# fl5_fl9_modv1.net
KiCad netlist of a schematic drawn in EAGLE
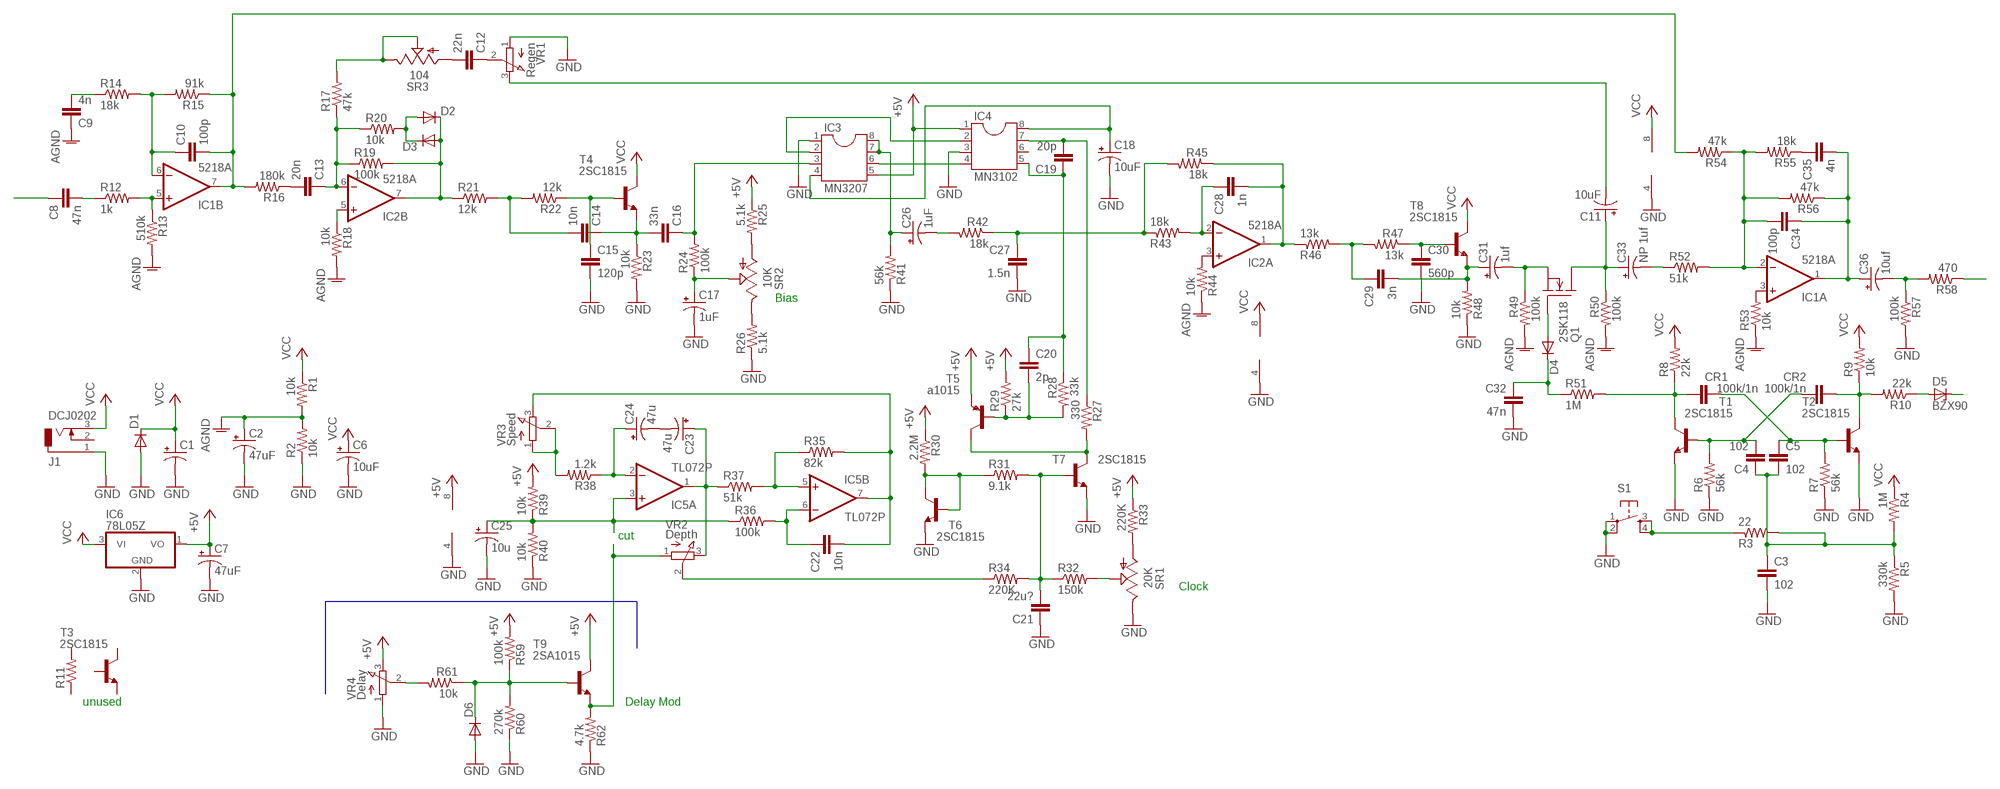
[diagram p0: schematic, sheet 1]

(export (version "E")
  (design (tool "Eeschema 10.0.6"))
  (components
    (comp (ref "C1")
      (value "CPOL-USE3.5-8")
      (footprint "eagle-import:E3,5-8")
      (libsource (lib "eagle-import") (part "CPOL-USE3.5-8"))
    )
    (comp (ref "C2")
      (value "47uF")
      (footprint "eagle-import:E1,8-4")
      (libsource (lib "eagle-import") (part "CPOL-USE1.8-4"))
    )
    (comp (ref "C3")
      (value "102")
      (footprint "eagle-import:C025-024X044")
      (libsource (lib "eagle-import") (part "C-EU025-024X044"))
    )
    (comp (ref "C4")
      (value "102")
      (footprint "eagle-import:C025-024X044")
      (libsource (lib "eagle-import") (part "C-EU025-024X044"))
    )
    (comp (ref "C5")
      (value "102")
      (footprint "eagle-import:C025-024X044")
      (libsource (lib "eagle-import") (part "C-EU025-024X044"))
    )
    (comp (ref "C6")
      (value "10uF")
      (footprint "eagle-import:E1,8-4")
      (libsource (lib "eagle-import") (part "CPOL-USE1.8-4"))
    )
    (comp (ref "C7")
      (value "47uF")
      (footprint "eagle-import:E1,8-4")
      (libsource (lib "eagle-import") (part "CPOL-USE1.8-4"))
    )
    (comp (ref "C8")
      (value "47n")
      (footprint "eagle-import:C050-025X075")
      (libsource (lib "eagle-import") (part "C-EU050-025X075"))
    )
    (comp (ref "C9")
      (value "4n")
      (footprint "eagle-import:C050-025X075")
      (libsource (lib "eagle-import") (part "C-EU050-025X075"))
    )
    (comp (ref "C10")
      (value "100p")
      (footprint "eagle-import:C025-024X044")
      (libsource (lib "eagle-import") (part "C-EU025-024X044"))
    )
    (comp (ref "C11")
      (value "10uF")
      (footprint "eagle-import:E1,8-4")
      (libsource (lib "eagle-import") (part "CPOL-USE1.8-4"))
    )
    (comp (ref "C12")
      (value "22n")
      (footprint "eagle-import:C050-025X075")
      (libsource (lib "eagle-import") (part "C-EU050-025X075"))
    )
    (comp (ref "C13")
      (value "20n")
      (footprint "eagle-import:C050-025X075")
      (libsource (lib "eagle-import") (part "C-EU050-025X075"))
    )
    (comp (ref "C14")
      (value "10n")
      (footprint "eagle-import:C050-025X075")
      (libsource (lib "eagle-import") (part "C-EU050-025X075"))
    )
    (comp (ref "C15")
      (value "120p")
      (footprint "eagle-import:C050-024X044")
      (libsource (lib "eagle-import") (part "C-EU050-024X044"))
    )
    (comp (ref "C16")
      (value "33n")
      (footprint "eagle-import:C050-025X075")
      (libsource (lib "eagle-import") (part "C-EU050-025X075"))
    )
    (comp (ref "C17")
      (value "1uF")
      (footprint "eagle-import:E1,8-4")
      (libsource (lib "eagle-import") (part "CPOL-USE1.8-4"))
    )
    (comp (ref "C18")
      (value "10uF")
      (footprint "eagle-import:E1,8-4")
      (libsource (lib "eagle-import") (part "CPOL-USE1.8-4"))
    )
    (comp (ref "C19")
      (value "20p")
      (footprint "eagle-import:C025-024X044")
      (libsource (lib "eagle-import") (part "C-EU025-024X044"))
    )
    (comp (ref "C20")
      (value "2p")
      (footprint "eagle-import:C025-024X044")
      (libsource (lib "eagle-import") (part "C-EU025-024X044"))
    )
    (comp (ref "C21")
      (value "22u?")
      (footprint "eagle-import:C025-024X044")
      (libsource (lib "eagle-import") (part "C-EU025-024X044"))
    )
    (comp (ref "C22")
      (value "10n")
      (footprint "eagle-import:C050-025X075")
      (libsource (lib "eagle-import") (part "C-EU050-025X075"))
    )
    (comp (ref "C23")
      (value "47u")
      (footprint "eagle-import:E2,5-7")
      (libsource (lib "eagle-import") (part "CPOL-USE2.5-7"))
    )
    (comp (ref "C24")
      (value "47u")
      (footprint "eagle-import:E2,5-7")
      (libsource (lib "eagle-import") (part "CPOL-USE2.5-7"))
    )
    (comp (ref "C25")
      (value "10u")
      (footprint "eagle-import:E1,8-4")
      (libsource (lib "eagle-import") (part "CPOL-USE1.8-4"))
    )
    (comp (ref "C26")
      (value "1uF")
      (footprint "eagle-import:E1,8-4")
      (libsource (lib "eagle-import") (part "CPOL-USE1.8-4"))
    )
    (comp (ref "C27")
      (value "1.5n")
      (footprint "eagle-import:C050-025X075")
      (libsource (lib "eagle-import") (part "C-EU050-025X075"))
    )
    (comp (ref "C28")
      (value "1n")
      (footprint "eagle-import:C050-025X075")
      (libsource (lib "eagle-import") (part "C-EU050-025X075"))
    )
    (comp (ref "C29")
      (value "3n")
      (footprint "eagle-import:C050-025X075")
      (libsource (lib "eagle-import") (part "C-EU050-025X075"))
    )
    (comp (ref "C30")
      (value "560p")
      (footprint "eagle-import:C050-024X044")
      (libsource (lib "eagle-import") (part "C-EU050-024X044"))
    )
    (comp (ref "C31")
      (value "1uf")
      (footprint "eagle-import:E1,8-4")
      (libsource (lib "eagle-import") (part "CPOL-USE1.8-4"))
    )
    (comp (ref "C32")
      (value "47n")
      (footprint "eagle-import:C050-025X075")
      (libsource (lib "eagle-import") (part "C-EU050-025X075"))
    )
    (comp (ref "C33")
      (value "NP 1uf")
      (footprint "eagle-import:E1,8-4")
      (libsource (lib "eagle-import") (part "CPOL-USE1.8-4"))
    )
    (comp (ref "C34")
      (value "100p")
      (footprint "eagle-import:C025-024X044")
      (libsource (lib "eagle-import") (part "C-EU025-024X044"))
    )
    (comp (ref "C35")
      (value "4n")
      (footprint "eagle-import:C050-025X075")
      (libsource (lib "eagle-import") (part "C-EU050-025X075"))
    )
    (comp (ref "C36")
      (value "10uf")
      (footprint "eagle-import:E1,8-4")
      (libsource (lib "eagle-import") (part "CPOL-USE1.8-4"))
    )
    (comp (ref "CR1")
      (value "100k/1n")
      (footprint "eagle-import:C025-024X044")
      (libsource (lib "eagle-import") (part "C-EU025-024X044"))
    )
    (comp (ref "CR2")
      (value "100k/1n")
      (footprint "eagle-import:C025-024X044")
      (libsource (lib "eagle-import") (part "C-EU025-024X044"))
    )
    (comp (ref "D1")
      (value "DIODE-C1702-05")
      (footprint "eagle-import:C1702-05")
      (libsource (lib "eagle-import") (part "DIODE-C1702-05"))
    )
    (comp (ref "D2")
      (value "DIODE-D-5")
      (footprint "eagle-import:D-5")
      (libsource (lib "eagle-import") (part "DIODE-D-5"))
    )
    (comp (ref "D3")
      (value "DIODE-D-5")
      (footprint "eagle-import:D-5")
      (libsource (lib "eagle-import") (part "DIODE-D-5"))
    )
    (comp (ref "D4")
      (value "DIODE-D-5")
      (footprint "eagle-import:D-5")
      (libsource (lib "eagle-import") (part "DIODE-D-5"))
    )
    (comp (ref "D5")
      (value "BZX90")
      (footprint "eagle-import:DO34Z7")
      (libsource (lib "eagle-import") (part "BZX90"))
    )
    (comp (ref "D6")
      (value "DIODE-D-5")
      (footprint "eagle-import:D-5")
      (libsource (lib "eagle-import") (part "DIODE-D-5"))
    )
    (comp (ref "IC1")
      (value "5218A")
      (footprint "eagle-import:DIL08")
      (libsource (lib "eagle-import") (part "4558NLM"))
    )
    (comp (ref "IC2")
      (value "5218A")
      (footprint "eagle-import:DIL08")
      (libsource (lib "eagle-import") (part "4558NLM"))
    )
    (comp (ref "IC3")
      (value "MN3207")
      (footprint "eagle-import:DIL08")
      (libsource (lib "eagle-import") (part "DIL8"))
    )
    (comp (ref "IC4")
      (value "MN3102")
      (footprint "eagle-import:DIL08")
      (libsource (lib "eagle-import") (part "DIL8"))
    )
    (comp (ref "IC5")
      (value "TL072P")
      (footprint "eagle-import:DIL08")
      (libsource (lib "eagle-import") (part "TL072P"))
    )
    (comp (ref "IC6")
      (value "78L05Z")
      (footprint "eagle-import:TO92")
      (libsource (lib "eagle-import") (part "78ZL05"))
    )
    (comp (ref "J1")
      (value "DCJ0202")
      (footprint "eagle-import:DCJ0202")
      (libsource (lib "eagle-import") (part "DCJ0202"))
    )
    (comp (ref "Q1")
      (value "2SK118")
      (footprint "eagle-import:TO237")
      (libsource (lib "eagle-import") (part "VN2222KM"))
    )
    (comp (ref "R1")
      (value "10k")
      (footprint "eagle-import:0204_5")
      (libsource (lib "eagle-import") (part "R-US_0204/5"))
    )
    (comp (ref "R2")
      (value "10k")
      (footprint "eagle-import:0204_5")
      (libsource (lib "eagle-import") (part "R-US_0204/5"))
    )
    (comp (ref "R3")
      (value "22")
      (footprint "eagle-import:0204_5")
      (libsource (lib "eagle-import") (part "R-US_0204/5"))
    )
    (comp (ref "R4")
      (value "1M")
      (footprint "eagle-import:0204_5")
      (libsource (lib "eagle-import") (part "R-US_0204/5"))
    )
    (comp (ref "R5")
      (value "330k")
      (footprint "eagle-import:0204_5")
      (libsource (lib "eagle-import") (part "R-US_0204/5"))
    )
    (comp (ref "R6")
      (value "56k")
      (footprint "eagle-import:0204_5")
      (libsource (lib "eagle-import") (part "R-US_0204/5"))
    )
    (comp (ref "R7")
      (value "56k")
      (footprint "eagle-import:0204_5")
      (libsource (lib "eagle-import") (part "R-US_0204/5"))
    )
    (comp (ref "R8")
      (value "22k")
      (footprint "eagle-import:0204_5")
      (libsource (lib "eagle-import") (part "R-US_0204/5"))
    )
    (comp (ref "R9")
      (value "10k")
      (footprint "eagle-import:0204_5")
      (libsource (lib "eagle-import") (part "R-US_0204/5"))
    )
    (comp (ref "R10")
      (value "22k")
      (footprint "eagle-import:0204_5")
      (libsource (lib "eagle-import") (part "R-US_0204/5"))
    )
    (comp (ref "R11")
      (value "R-US_0204/5")
      (footprint "eagle-import:0204_5")
      (libsource (lib "eagle-import") (part "R-US_0204/5"))
    )
    (comp (ref "R12")
      (value "1k")
      (footprint "eagle-import:0204_5")
      (libsource (lib "eagle-import") (part "R-US_0204/5"))
    )
    (comp (ref "R13")
      (value "510k")
      (footprint "eagle-import:0204_5")
      (libsource (lib "eagle-import") (part "R-US_0204/5"))
    )
    (comp (ref "R14")
      (value "18k")
      (footprint "eagle-import:0204_5")
      (libsource (lib "eagle-import") (part "R-US_0204/5"))
    )
    (comp (ref "R15")
      (value "91k")
      (footprint "eagle-import:0204_5")
      (libsource (lib "eagle-import") (part "R-US_0204/5"))
    )
    (comp (ref "R16")
      (value "180k")
      (footprint "eagle-import:0204_5")
      (libsource (lib "eagle-import") (part "R-US_0204/5"))
    )
    (comp (ref "R17")
      (value "47k")
      (footprint "eagle-import:0204_5")
      (libsource (lib "eagle-import") (part "R-US_0204/5"))
    )
    (comp (ref "R18")
      (value "10k")
      (footprint "eagle-import:0204_5")
      (libsource (lib "eagle-import") (part "R-US_0204/5"))
    )
    (comp (ref "R19")
      (value "100k")
      (footprint "eagle-import:0204_5")
      (libsource (lib "eagle-import") (part "R-US_0204/5"))
    )
    (comp (ref "R20")
      (value "10k")
      (footprint "eagle-import:0204_5")
      (libsource (lib "eagle-import") (part "R-US_0204/5"))
    )
    (comp (ref "R21")
      (value "12k")
      (footprint "eagle-import:0204_5")
      (libsource (lib "eagle-import") (part "R-US_0204/5"))
    )
    (comp (ref "R22")
      (value "12k")
      (footprint "eagle-import:0204_5")
      (libsource (lib "eagle-import") (part "R-US_0204/5"))
    )
    (comp (ref "R23")
      (value "10k")
      (footprint "eagle-import:0204_5")
      (libsource (lib "eagle-import") (part "R-US_0204/5"))
    )
    (comp (ref "R24")
      (value "100k")
      (footprint "eagle-import:0204_5")
      (libsource (lib "eagle-import") (part "R-US_0204/5"))
    )
    (comp (ref "R25")
      (value "5.1k")
      (footprint "eagle-import:0204_5")
      (libsource (lib "eagle-import") (part "R-US_0204/5"))
    )
    (comp (ref "R26")
      (value "5.1k")
      (footprint "eagle-import:0204_5")
      (libsource (lib "eagle-import") (part "R-US_0204/5"))
    )
    (comp (ref "R27")
      (value "330")
      (footprint "eagle-import:0204_5")
      (libsource (lib "eagle-import") (part "R-US_0204/5"))
    )
    (comp (ref "R28")
      (value "33k")
      (footprint "eagle-import:0204_5")
      (libsource (lib "eagle-import") (part "R-US_0204/5"))
    )
    (comp (ref "R29")
      (value "27k")
      (footprint "eagle-import:0204_5")
      (libsource (lib "eagle-import") (part "R-US_0204/5"))
    )
    (comp (ref "R30")
      (value "2.2M")
      (footprint "eagle-import:0204_5")
      (libsource (lib "eagle-import") (part "R-US_0204/5"))
    )
    (comp (ref "R31")
      (value "9.1k")
      (footprint "eagle-import:0204_5")
      (libsource (lib "eagle-import") (part "R-US_0204/5"))
    )
    (comp (ref "R32")
      (value "150k")
      (footprint "eagle-import:0204_5")
      (libsource (lib "eagle-import") (part "R-US_0204/5"))
    )
    (comp (ref "R33")
      (value "220K")
      (footprint "eagle-import:0204_5")
      (libsource (lib "eagle-import") (part "R-US_0204/5"))
    )
    (comp (ref "R34")
      (value "220K")
      (footprint "eagle-import:0204_5")
      (libsource (lib "eagle-import") (part "R-US_0204/5"))
    )
    (comp (ref "R35")
      (value "82k")
      (footprint "eagle-import:0204_5")
      (libsource (lib "eagle-import") (part "R-US_0204/5"))
    )
    (comp (ref "R36")
      (value "100k")
      (footprint "eagle-import:0204_5")
      (libsource (lib "eagle-import") (part "R-US_0204/5"))
    )
    (comp (ref "R37")
      (value "51k")
      (footprint "eagle-import:0204_5")
      (libsource (lib "eagle-import") (part "R-US_0204/5"))
    )
    (comp (ref "R38")
      (value "1.2k")
      (footprint "eagle-import:0204_5")
      (libsource (lib "eagle-import") (part "R-US_0204/5"))
    )
    (comp (ref "R39")
      (value "10k")
      (footprint "eagle-import:0204_5")
      (libsource (lib "eagle-import") (part "R-US_0204/5"))
    )
    (comp (ref "R40")
      (value "10k")
      (footprint "eagle-import:0204_5")
      (libsource (lib "eagle-import") (part "R-US_0204/5"))
    )
    (comp (ref "R41")
      (value "56k")
      (footprint "eagle-import:0204_5")
      (libsource (lib "eagle-import") (part "R-US_0204/5"))
    )
    (comp (ref "R42")
      (value "18k")
      (footprint "eagle-import:0204_5")
      (libsource (lib "eagle-import") (part "R-US_0204/5"))
    )
    (comp (ref "R43")
      (value "18k")
      (footprint "eagle-import:0204_5")
      (libsource (lib "eagle-import") (part "R-US_0204/5"))
    )
    (comp (ref "R44")
      (value "10k")
      (footprint "eagle-import:0204_5")
      (libsource (lib "eagle-import") (part "R-US_0204/5"))
    )
    (comp (ref "R45")
      (value "18k")
      (footprint "eagle-import:0204_5")
      (libsource (lib "eagle-import") (part "R-US_0204/5"))
    )
    (comp (ref "R46")
      (value "13k")
      (footprint "eagle-import:0204_5")
      (libsource (lib "eagle-import") (part "R-US_0204/5"))
    )
    (comp (ref "R47")
      (value "13k")
      (footprint "eagle-import:0204_5")
      (libsource (lib "eagle-import") (part "R-US_0204/5"))
    )
    (comp (ref "R48")
      (value "10k")
      (footprint "eagle-import:0204_5")
      (libsource (lib "eagle-import") (part "R-US_0204/5"))
    )
    (comp (ref "R49")
      (value "100k")
      (footprint "eagle-import:0204_5")
      (libsource (lib "eagle-import") (part "R-US_0204/5"))
    )
    (comp (ref "R50")
      (value "100k")
      (footprint "eagle-import:0204_5")
      (libsource (lib "eagle-import") (part "R-US_0204/5"))
    )
    (comp (ref "R51")
      (value "1M")
      (footprint "eagle-import:0204_5")
      (libsource (lib "eagle-import") (part "R-US_0204/5"))
    )
    (comp (ref "R52")
      (value "51k")
      (footprint "eagle-import:0204_5")
      (libsource (lib "eagle-import") (part "R-US_0204/5"))
    )
    (comp (ref "R53")
      (value "10k")
      (footprint "eagle-import:0204_5")
      (libsource (lib "eagle-import") (part "R-US_0204/5"))
    )
    (comp (ref "R54")
      (value "47k")
      (footprint "eagle-import:0204_5")
      (libsource (lib "eagle-import") (part "R-US_0204/5"))
    )
    (comp (ref "R55")
      (value "18k")
      (footprint "eagle-import:0204_5")
      (libsource (lib "eagle-import") (part "R-US_0204/5"))
    )
    (comp (ref "R56")
      (value "47k")
      (footprint "eagle-import:0204_5")
      (libsource (lib "eagle-import") (part "R-US_0204/5"))
    )
    (comp (ref "R57")
      (value "100k")
      (footprint "eagle-import:0204_5")
      (libsource (lib "eagle-import") (part "R-US_0204/5"))
    )
    (comp (ref "R58")
      (value "470")
      (footprint "eagle-import:0204_5")
      (libsource (lib "eagle-import") (part "R-US_0204/5"))
    )
    (comp (ref "R59")
      (value "100k")
      (footprint "eagle-import:0204_5")
      (libsource (lib "eagle-import") (part "R-US_0204/5"))
    )
    (comp (ref "R60")
      (value "270k")
      (footprint "eagle-import:0204_5")
      (libsource (lib "eagle-import") (part "R-US_0204/5"))
    )
    (comp (ref "R61")
      (value "10k")
      (footprint "eagle-import:0204_5")
      (libsource (lib "eagle-import") (part "R-US_0204/5"))
    )
    (comp (ref "R62")
      (value "4.7k")
      (footprint "eagle-import:0204_5")
      (libsource (lib "eagle-import") (part "R-US_0204/5"))
    )
    (comp (ref "S1")
      (value "TAC_SWITCHPTH")
      (footprint "eagle-import:TACTILE-PTH")
      (libsource (lib "eagle-import") (part "TAC_SWITCHPTH"))
    )
    (comp (ref "SR1")
      (value "20K")
      (footprint "eagle-import:CA6V")
      (libsource (lib "eagle-import") (part "TRIM_US-CA6V"))
    )
    (comp (ref "SR2")
      (value "10K")
      (footprint "eagle-import:CA6V")
      (libsource (lib "eagle-import") (part "TRIM_US-CA6V"))
    )
    (comp (ref "SR3")
      (value "104")
      (footprint "eagle-import:CA6V")
      (libsource (lib "eagle-import") (part "TRIM_US-CA6V"))
    )
    (comp (ref "T1")
      (value "2SC1815")
      (footprint "eagle-import:TO92-ECB")
      (libsource (lib "eagle-import") (part "2SC1815"))
    )
    (comp (ref "T2")
      (value "2SC1815")
      (footprint "eagle-import:TO92-ECB")
      (libsource (lib "eagle-import") (part "2SC1815"))
    )
    (comp (ref "T3")
      (value "2SC1815")
      (footprint "eagle-import:TO92-ECB")
      (libsource (lib "eagle-import") (part "2SC1815"))
    )
    (comp (ref "T4")
      (value "2SC1815")
      (footprint "eagle-import:TO92-ECB")
      (libsource (lib "eagle-import") (part "2SC1815"))
    )
    (comp (ref "T5")
      (value "a1015")
      (footprint "eagle-import:TO92-ECB")
      (libsource (lib "eagle-import") (part "-PNP-TO92-ECB"))
    )
    (comp (ref "T6")
      (value "2SC1815")
      (footprint "eagle-import:TO92-ECB")
      (libsource (lib "eagle-import") (part "2SC1815"))
    )
    (comp (ref "T7")
      (value "2SC1815")
      (footprint "eagle-import:TO92-ECB")
      (libsource (lib "eagle-import") (part "2SC1815"))
    )
    (comp (ref "T8")
      (value "2SC1815")
      (footprint "eagle-import:TO92-ECB")
      (libsource (lib "eagle-import") (part "2SC1815"))
    )
    (comp (ref "T9")
      (value "2SA1015")
      (footprint "eagle-import:TO92-ECB")
      (libsource (lib "eagle-import") (part "2SC1815"))
    )
    (comp (ref "VR1")
      (value "Regen")
      (footprint "eagle-import:EVUF")
      (libsource (lib "eagle-import") (part "EVUAF2"))
    )
    (comp (ref "VR2")
      (value "Depth")
      (footprint "eagle-import:EVUF")
      (libsource (lib "eagle-import") (part "EVUAF2"))
    )
    (comp (ref "VR3")
      (value "Speed")
      (footprint "eagle-import:EVUF")
      (libsource (lib "eagle-import") (part "EVUAF2"))
    )
    (comp (ref "VR4")
      (value "Delay")
      (footprint "eagle-import:EVUF")
      (libsource (lib "eagle-import") (part "EVUAF2"))
    )
  )
  (nets
    (net (code "1") (name "+5V") (class "Default")
      (node (ref "C7") (pin "+") (pinfunction "+_+") (pintype "passive"))
      (node (ref "IC3") (pin "5") (pinfunction "5_5") (pintype "passive"))
      (node (ref "IC4") (pin "1") (pinfunction "1_1") (pintype "passive"))
      (node (ref "IC5") (pin "8") (pinfunction "V+_8") (pintype "power_in"))
      (node (ref "IC6") (pin "1") (pinfunction "VO_1") (pintype "passive"))
      (node (ref "R25") (pin "1") (pinfunction "1_1") (pintype "passive"))
      (node (ref "R29") (pin "2") (pinfunction "2_2") (pintype "passive"))
      (node (ref "R30") (pin "1") (pinfunction "1_1") (pintype "passive"))
      (node (ref "R33") (pin "1") (pinfunction "1_1") (pintype "passive"))
      (node (ref "R39") (pin "2") (pinfunction "2_2") (pintype "passive"))
      (node (ref "R59") (pin "2") (pinfunction "2_2") (pintype "passive"))
      (node (ref "T5") (pin "E") (pinfunction "E_E") (pintype "passive"))
      (node (ref "T9") (pin "C") (pinfunction "C_C") (pintype "passive"))
      (node (ref "VR4") (pin "3") (pinfunction "E_3") (pintype "passive"))
    )
    (net (code "2") (name "AGND") (class "Default")
      (node (ref "C2") (pin "+") (pinfunction "+_+") (pintype "passive"))
      (node (ref "C9") (pin "1") (pinfunction "1_1") (pintype "passive"))
      (node (ref "R1") (pin "2") (pinfunction "2_2") (pintype "passive"))
      (node (ref "R13") (pin "2") (pinfunction "2_2") (pintype "passive"))
      (node (ref "R18") (pin "2") (pinfunction "2_2") (pintype "passive"))
      (node (ref "R2") (pin "2") (pinfunction "2_2") (pintype "passive"))
      (node (ref "R44") (pin "1") (pinfunction "1_1") (pintype "passive"))
      (node (ref "R49") (pin "2") (pinfunction "2_2") (pintype "passive"))
      (node (ref "R50") (pin "2") (pinfunction "2_2") (pintype "passive"))
      (node (ref "R53") (pin "1") (pinfunction "1_1") (pintype "passive"))
    )
    (net (code "3") (name "GND") (class "Default")
      (node (ref "C1") (pin "-") (pinfunction "-_-") (pintype "passive"))
      (node (ref "C15") (pin "2") (pinfunction "2_2") (pintype "passive"))
      (node (ref "C17") (pin "-") (pinfunction "-_-") (pintype "passive"))
      (node (ref "C18") (pin "-") (pinfunction "-_-") (pintype "passive"))
      (node (ref "C2") (pin "-") (pinfunction "-_-") (pintype "passive"))
      (node (ref "C21") (pin "1") (pinfunction "1_1") (pintype "passive"))
      (node (ref "C25") (pin "-") (pinfunction "-_-") (pintype "passive"))
      (node (ref "C27") (pin "2") (pinfunction "2_2") (pintype "passive"))
      (node (ref "C3") (pin "2") (pinfunction "2_2") (pintype "passive"))
      (node (ref "C30") (pin "2") (pinfunction "2_2") (pintype "passive"))
      (node (ref "C32") (pin "2") (pinfunction "2_2") (pintype "passive"))
      (node (ref "C6") (pin "-") (pinfunction "-_-") (pintype "passive"))
      (node (ref "C7") (pin "-") (pinfunction "-_-") (pintype "passive"))
      (node (ref "D1") (pin "A") (pinfunction "A_A") (pintype "passive"))
      (node (ref "D6") (pin "A") (pinfunction "A_A") (pintype "passive"))
      (node (ref "IC1") (pin "4") (pinfunction "V-_4") (pintype "power_in"))
      (node (ref "IC2") (pin "4") (pinfunction "V-_4") (pintype "power_in"))
      (node (ref "IC3") (pin "1") (pinfunction "1_1") (pintype "passive"))
      (node (ref "IC4") (pin "3") (pinfunction "3_3") (pintype "passive"))
      (node (ref "IC5") (pin "4") (pinfunction "V-_4") (pintype "power_in"))
      (node (ref "IC6") (pin "2") (pinfunction "GND_2") (pintype "passive"))
      (node (ref "J1") (pin "1") (pinfunction "1_1") (pintype "passive"))
      (node (ref "R2") (pin "1") (pinfunction "1_1") (pintype "passive"))
      (node (ref "R23") (pin "2") (pinfunction "2_2") (pintype "passive"))
      (node (ref "R26") (pin "1") (pinfunction "1_1") (pintype "passive"))
      (node (ref "R40") (pin "1") (pinfunction "1_1") (pintype "passive"))
      (node (ref "R41") (pin "1") (pinfunction "1_1") (pintype "passive"))
      (node (ref "R48") (pin "1") (pinfunction "1_1") (pintype "passive"))
      (node (ref "R5") (pin "2") (pinfunction "2_2") (pintype "passive"))
      (node (ref "R57") (pin "2") (pinfunction "2_2") (pintype "passive"))
      (node (ref "R6") (pin "1") (pinfunction "1_1") (pintype "passive"))
      (node (ref "R60") (pin "1") (pinfunction "1_1") (pintype "passive"))
      (node (ref "R62") (pin "1") (pinfunction "1_1") (pintype "passive"))
      (node (ref "R7") (pin "1") (pinfunction "1_1") (pintype "passive"))
      (node (ref "S1") (pin "1") (pinfunction "1_1") (pintype "passive"))
      (node (ref "S1") (pin "2") (pinfunction "2_2") (pintype "passive"))
      (node (ref "SR1") (pin "E") (pinfunction "E_E") (pintype "passive"))
      (node (ref "T1") (pin "E") (pinfunction "E_E") (pintype "passive"))
      (node (ref "T2") (pin "E") (pinfunction "E_E") (pintype "passive"))
      (node (ref "T6") (pin "E") (pinfunction "E_E") (pintype "passive"))
      (node (ref "T7") (pin "E") (pinfunction "E_E") (pintype "passive"))
      (node (ref "VR1") (pin "1") (pinfunction "A_1") (pintype "passive"))
      (node (ref "VR4") (pin "1") (pinfunction "A_1") (pintype "passive"))
    )
    (net (code "4") (name "Net-(C3-Pad1)") (class "Default")
      (node (ref "C3") (pin "1") (pinfunction "1_1") (pintype "passive"))
      (node (ref "C4") (pin "1") (pinfunction "1_1") (pintype "passive"))
      (node (ref "C5") (pin "2") (pinfunction "2_2") (pintype "passive"))
      (node (ref "R3") (pin "2") (pinfunction "2_2") (pintype "passive"))
      (node (ref "R4") (pin "2") (pinfunction "2_2") (pintype "passive"))
      (node (ref "R5") (pin "1") (pinfunction "1_1") (pintype "passive"))
    )
    (net (code "5") (name "Net-(C4-Pad2)") (class "Default")
      (node (ref "C4") (pin "2") (pinfunction "2_2") (pintype "passive"))
      (node (ref "CR2") (pin "2") (pinfunction "2_2") (pintype "passive"))
      (node (ref "R6") (pin "2") (pinfunction "2_2") (pintype "passive"))
      (node (ref "T1") (pin "B") (pinfunction "B_B") (pintype "passive"))
    )
    (net (code "6") (name "Net-(C5-Pad1)") (class "Default")
      (node (ref "C5") (pin "1") (pinfunction "1_1") (pintype "passive"))
      (node (ref "CR1") (pin "1") (pinfunction "1_1") (pintype "passive"))
      (node (ref "R7") (pin "2") (pinfunction "2_2") (pintype "passive"))
      (node (ref "T2") (pin "B") (pinfunction "B_B") (pintype "passive"))
    )
    (net (code "7") (name "Net-(C8-Pad2)") (class "Default")
      (node (ref "C8") (pin "2") (pinfunction "2_2") (pintype "passive"))
      (node (ref "R12") (pin "1") (pinfunction "1_1") (pintype "passive"))
    )
    (net (code "8") (name "Net-(C9-Pad2)") (class "Default")
      (node (ref "C9") (pin "2") (pinfunction "2_2") (pintype "passive"))
      (node (ref "R14") (pin "1") (pinfunction "1_1") (pintype "passive"))
    )
    (net (code "9") (name "Net-(C12-Pad2)") (class "Default")
      (node (ref "C12") (pin "2") (pinfunction "2_2") (pintype "passive"))
      (node (ref "SR3") (pin "A") (pinfunction "A_A") (pintype "passive"))
    )
    (net (code "10") (name "Net-(C13-Pad2)") (class "Default")
      (node (ref "C13") (pin "2") (pinfunction "2_2") (pintype "passive"))
      (node (ref "R16") (pin "1") (pinfunction "1_1") (pintype "passive"))
    )
    (net (code "11") (name "Net-(C14-Pad1)") (class "Default")
      (node (ref "C14") (pin "1") (pinfunction "1_1") (pintype "passive"))
      (node (ref "C16") (pin "2") (pinfunction "2_2") (pintype "passive"))
      (node (ref "R23") (pin "1") (pinfunction "1_1") (pintype "passive"))
      (node (ref "T4") (pin "E") (pinfunction "E_E") (pintype "passive"))
    )
    (net (code "12") (name "Net-(C14-Pad2)") (class "Default")
      (node (ref "C14") (pin "2") (pinfunction "2_2") (pintype "passive"))
      (node (ref "R21") (pin "2") (pinfunction "2_2") (pintype "passive"))
      (node (ref "R22") (pin "2") (pinfunction "2_2") (pintype "passive"))
    )
    (net (code "13") (name "Net-(C15-Pad1)") (class "Default")
      (node (ref "C15") (pin "1") (pinfunction "1_1") (pintype "passive"))
      (node (ref "R22") (pin "1") (pinfunction "1_1") (pintype "passive"))
      (node (ref "T4") (pin "B") (pinfunction "B_B") (pintype "passive"))
    )
    (net (code "14") (name "Net-(C16-Pad1)") (class "Default")
      (node (ref "C16") (pin "1") (pinfunction "1_1") (pintype "passive"))
      (node (ref "IC3") (pin "3") (pinfunction "3_3") (pintype "passive"))
      (node (ref "R24") (pin "2") (pinfunction "2_2") (pintype "passive"))
    )
    (net (code "15") (name "Net-(C17-Pad+)") (class "Default")
      (node (ref "C17") (pin "+") (pinfunction "+_+") (pintype "passive"))
      (node (ref "R24") (pin "1") (pinfunction "1_1") (pintype "passive"))
      (node (ref "SR2") (pin "S") (pinfunction "S_S") (pintype "passive"))
    )
    (net (code "16") (name "Net-(C18-Pad+)") (class "Default")
      (node (ref "C18") (pin "+") (pinfunction "+_+") (pintype "passive"))
      (node (ref "IC3") (pin "4") (pinfunction "4_4") (pintype "passive"))
      (node (ref "IC4") (pin "8") (pinfunction "8_8") (pintype "passive"))
    )
    (net (code "17") (name "Net-(C19-Pad1)") (class "Default")
      (node (ref "C19") (pin "1") (pinfunction "1_1") (pintype "passive"))
      (node (ref "C20") (pin "1") (pinfunction "1_1") (pintype "passive"))
      (node (ref "IC4") (pin "5") (pinfunction "5_5") (pintype "passive"))
      (node (ref "R28") (pin "1") (pinfunction "1_1") (pintype "passive"))
    )
    (net (code "18") (name "Net-(C19-Pad2)") (class "Default")
      (node (ref "C19") (pin "2") (pinfunction "2_2") (pintype "passive"))
      (node (ref "IC4") (pin "7") (pinfunction "7_7") (pintype "passive"))
      (node (ref "R27") (pin "1") (pinfunction "1_1") (pintype "passive"))
    )
    (net (code "19") (name "Net-(C20-Pad2)") (class "Default")
      (node (ref "C20") (pin "2") (pinfunction "2_2") (pintype "passive"))
      (node (ref "R28") (pin "2") (pinfunction "2_2") (pintype "passive"))
      (node (ref "R29") (pin "1") (pinfunction "1_1") (pintype "passive"))
      (node (ref "T5") (pin "B") (pinfunction "B_B") (pintype "passive"))
    )
    (net (code "20") (name "Net-(C21-Pad2)") (class "Default")
      (node (ref "C21") (pin "2") (pinfunction "2_2") (pintype "passive"))
      (node (ref "R31") (pin "2") (pinfunction "2_2") (pintype "passive"))
      (node (ref "R32") (pin "1") (pinfunction "1_1") (pintype "passive"))
      (node (ref "R34") (pin "2") (pinfunction "2_2") (pintype "passive"))
      (node (ref "T7") (pin "B") (pinfunction "B_B") (pintype "passive"))
    )
    (net (code "21") (name "Net-(C23-Pad-)") (class "Default")
      (node (ref "C23") (pin "-") (pinfunction "-_-") (pintype "passive"))
      (node (ref "C24") (pin "-") (pinfunction "-_-") (pintype "passive"))
    )
    (net (code "22") (name "Net-(C26-Pad+)") (class "Default")
      (node (ref "C26") (pin "+") (pinfunction "+_+") (pintype "passive"))
      (node (ref "IC3") (pin "7") (pinfunction "7_7") (pintype "passive"))
      (node (ref "IC3") (pin "8") (pinfunction "8_8") (pintype "passive"))
      (node (ref "R41") (pin "2") (pinfunction "2_2") (pintype "passive"))
    )
    (net (code "23") (name "Net-(C26-Pad-)") (class "Default")
      (node (ref "C26") (pin "-") (pinfunction "-_-") (pintype "passive"))
      (node (ref "R42") (pin "2") (pinfunction "2_2") (pintype "passive"))
    )
    (net (code "24") (name "Net-(C27-Pad1)") (class "Default")
      (node (ref "C27") (pin "1") (pinfunction "1_1") (pintype "passive"))
      (node (ref "R42") (pin "1") (pinfunction "1_1") (pintype "passive"))
      (node (ref "R43") (pin "1") (pinfunction "1_1") (pintype "passive"))
      (node (ref "R45") (pin "2") (pinfunction "2_2") (pintype "passive"))
    )
    (net (code "25") (name "Net-(C29-Pad1)") (class "Default")
      (node (ref "C29") (pin "1") (pinfunction "1_1") (pintype "passive"))
      (node (ref "R46") (pin "2") (pinfunction "2_2") (pintype "passive"))
      (node (ref "R47") (pin "2") (pinfunction "2_2") (pintype "passive"))
    )
    (net (code "26") (name "Net-(C29-Pad2)") (class "Default")
      (node (ref "C29") (pin "2") (pinfunction "2_2") (pintype "passive"))
      (node (ref "C31") (pin "+") (pinfunction "+_+") (pintype "passive"))
      (node (ref "R48") (pin "2") (pinfunction "2_2") (pintype "passive"))
      (node (ref "T8") (pin "E") (pinfunction "E_E") (pintype "passive"))
    )
    (net (code "27") (name "Net-(C30-Pad1)") (class "Default")
      (node (ref "C30") (pin "1") (pinfunction "1_1") (pintype "passive"))
      (node (ref "R47") (pin "1") (pinfunction "1_1") (pintype "passive"))
      (node (ref "T8") (pin "B") (pinfunction "B_B") (pintype "passive"))
    )
    (net (code "28") (name "Net-(C32-Pad1)") (class "Default")
      (node (ref "C32") (pin "1") (pinfunction "1_1") (pintype "passive"))
      (node (ref "D4") (pin "C") (pinfunction "C_C") (pintype "passive"))
      (node (ref "R51") (pin "1") (pinfunction "1_1") (pintype "passive"))
    )
    (net (code "29") (name "Net-(C33-Pad-)") (class "Default")
      (node (ref "C33") (pin "-") (pinfunction "-_-") (pintype "passive"))
      (node (ref "R52") (pin "1") (pinfunction "1_1") (pintype "passive"))
    )
    (net (code "30") (name "Net-(C35-Pad1)") (class "Default")
      (node (ref "C35") (pin "1") (pinfunction "1_1") (pintype "passive"))
      (node (ref "R55") (pin "1") (pinfunction "1_1") (pintype "passive"))
    )
    (net (code "31") (name "Net-(C36-Pad-)") (class "Default")
      (node (ref "C36") (pin "-") (pinfunction "-_-") (pintype "passive"))
      (node (ref "R57") (pin "1") (pinfunction "1_1") (pintype "passive"))
      (node (ref "R58") (pin "2") (pinfunction "2_2") (pintype "passive"))
    )
    (net (code "32") (name "Net-(CR1-Pad2)") (class "Default")
      (node (ref "CR1") (pin "2") (pinfunction "2_2") (pintype "passive"))
      (node (ref "R51") (pin "2") (pinfunction "2_2") (pintype "passive"))
      (node (ref "R8") (pin "1") (pinfunction "1_1") (pintype "passive"))
      (node (ref "T1") (pin "C") (pinfunction "C_C") (pintype "passive"))
    )
    (net (code "33") (name "Net-(CR2-Pad1)") (class "Default")
      (node (ref "CR2") (pin "1") (pinfunction "1_1") (pintype "passive"))
      (node (ref "R10") (pin "2") (pinfunction "2_2") (pintype "passive"))
      (node (ref "R9") (pin "1") (pinfunction "1_1") (pintype "passive"))
      (node (ref "T2") (pin "C") (pinfunction "C_C") (pintype "passive"))
    )
    (net (code "34") (name "Net-(D2-PadA)") (class "Default")
      (node (ref "D2") (pin "A") (pinfunction "A_A") (pintype "passive"))
      (node (ref "D3") (pin "C") (pinfunction "C_C") (pintype "passive"))
      (node (ref "R20") (pin "2") (pinfunction "2_2") (pintype "passive"))
    )
    (net (code "35") (name "Net-(D5-PadA)") (class "Default")
      (node (ref "D5") (pin "A") (pinfunction "A_A") (pintype "passive"))
      (node (ref "R10") (pin "1") (pinfunction "1_1") (pintype "passive"))
    )
    (net (code "36") (name "Net-(D6-PadC)") (class "Default")
      (node (ref "D6") (pin "C") (pinfunction "C_C") (pintype "passive"))
      (node (ref "R59") (pin "1") (pinfunction "1_1") (pintype "passive"))
      (node (ref "R60") (pin "2") (pinfunction "2_2") (pintype "passive"))
      (node (ref "R61") (pin "1") (pinfunction "1_1") (pintype "passive"))
      (node (ref "T9") (pin "B") (pinfunction "B_B") (pintype "passive"))
    )
    (net (code "37") (name "Net-(IC1A-+IN)") (class "Default")
      (node (ref "IC1") (pin "3") (pinfunction "+IN_3") (pintype "input"))
      (node (ref "R53") (pin "2") (pinfunction "2_2") (pintype "passive"))
    )
    (net (code "38") (name "Net-(IC1A--IN)") (class "Default")
      (node (ref "C34") (pin "2") (pinfunction "2_2") (pintype "passive"))
      (node (ref "IC1") (pin "2") (pinfunction "-IN_2") (pintype "input"))
      (node (ref "R52") (pin "2") (pinfunction "2_2") (pintype "passive"))
      (node (ref "R54") (pin "1") (pinfunction "1_1") (pintype "passive"))
      (node (ref "R55") (pin "2") (pinfunction "2_2") (pintype "passive"))
      (node (ref "R56") (pin "2") (pinfunction "2_2") (pintype "passive"))
    )
    (net (code "39") (name "Net-(IC1A-OUT)") (class "Default")
      (node (ref "C34") (pin "1") (pinfunction "1_1") (pintype "passive"))
      (node (ref "C35") (pin "2") (pinfunction "2_2") (pintype "passive"))
      (node (ref "C36") (pin "+") (pinfunction "+_+") (pintype "passive"))
      (node (ref "IC1") (pin "1") (pinfunction "OUT_1") (pintype "output"))
      (node (ref "R56") (pin "1") (pinfunction "1_1") (pintype "passive"))
    )
    (net (code "40") (name "Net-(IC1B-+IN)") (class "Default")
      (node (ref "IC1") (pin "5") (pinfunction "+IN_5") (pintype "input"))
      (node (ref "R12") (pin "2") (pinfunction "2_2") (pintype "passive"))
      (node (ref "R13") (pin "1") (pinfunction "1_1") (pintype "passive"))
    )
    (net (code "41") (name "Net-(IC1B--IN)") (class "Default")
      (node (ref "C10") (pin "1") (pinfunction "1_1") (pintype "passive"))
      (node (ref "IC1") (pin "6") (pinfunction "-IN_6") (pintype "input"))
      (node (ref "R14") (pin "2") (pinfunction "2_2") (pintype "passive"))
      (node (ref "R15") (pin "2") (pinfunction "2_2") (pintype "passive"))
    )
    (net (code "42") (name "Net-(IC1B-OUT)") (class "Default")
      (node (ref "C10") (pin "2") (pinfunction "2_2") (pintype "passive"))
      (node (ref "IC1") (pin "7") (pinfunction "OUT_7") (pintype "output"))
      (node (ref "R15") (pin "1") (pinfunction "1_1") (pintype "passive"))
      (node (ref "R16") (pin "2") (pinfunction "2_2") (pintype "passive"))
      (node (ref "R54") (pin "2") (pinfunction "2_2") (pintype "passive"))
    )
    (net (code "43") (name "Net-(IC2A-+IN)") (class "Default")
      (node (ref "IC2") (pin "3") (pinfunction "+IN_3") (pintype "input"))
      (node (ref "R44") (pin "2") (pinfunction "2_2") (pintype "passive"))
    )
    (net (code "44") (name "Net-(IC2A--IN)") (class "Default")
      (node (ref "C28") (pin "1") (pinfunction "1_1") (pintype "passive"))
      (node (ref "IC2") (pin "2") (pinfunction "-IN_2") (pintype "input"))
      (node (ref "R43") (pin "2") (pinfunction "2_2") (pintype "passive"))
    )
    (net (code "45") (name "Net-(IC2A-OUT)") (class "Default")
      (node (ref "C28") (pin "2") (pinfunction "2_2") (pintype "passive"))
      (node (ref "IC2") (pin "1") (pinfunction "OUT_1") (pintype "output"))
      (node (ref "R45") (pin "1") (pinfunction "1_1") (pintype "passive"))
      (node (ref "R46") (pin "1") (pinfunction "1_1") (pintype "passive"))
    )
    (net (code "46") (name "Net-(IC2B-+IN)") (class "Default")
      (node (ref "IC2") (pin "5") (pinfunction "+IN_5") (pintype "input"))
      (node (ref "R18") (pin "1") (pinfunction "1_1") (pintype "passive"))
    )
    (net (code "47") (name "Net-(IC2B--IN)") (class "Default")
      (node (ref "C13") (pin "1") (pinfunction "1_1") (pintype "passive"))
      (node (ref "IC2") (pin "6") (pinfunction "-IN_6") (pintype "input"))
      (node (ref "R17") (pin "1") (pinfunction "1_1") (pintype "passive"))
      (node (ref "R19") (pin "1") (pinfunction "1_1") (pintype "passive"))
      (node (ref "R20") (pin "1") (pinfunction "1_1") (pintype "passive"))
    )
    (net (code "48") (name "Net-(IC2B-OUT)") (class "Default")
      (node (ref "D2") (pin "C") (pinfunction "C_C") (pintype "passive"))
      (node (ref "D3") (pin "A") (pinfunction "A_A") (pintype "passive"))
      (node (ref "IC2") (pin "7") (pinfunction "OUT_7") (pintype "output"))
      (node (ref "R19") (pin "2") (pinfunction "2_2") (pintype "passive"))
      (node (ref "R21") (pin "1") (pinfunction "1_1") (pintype "passive"))
    )
    (net (code "49") (name "Net-(IC3-Pad2)") (class "Default")
      (node (ref "IC3") (pin "2") (pinfunction "2_2") (pintype "passive"))
      (node (ref "IC4") (pin "2") (pinfunction "2_2") (pintype "passive"))
    )
    (net (code "50") (name "Net-(IC3-Pad6)") (class "Default")
      (node (ref "IC3") (pin "6") (pinfunction "6_6") (pintype "passive"))
      (node (ref "IC4") (pin "4") (pinfunction "4_4") (pintype "passive"))
    )
    (net (code "51") (name "Net-(IC5A-+IN)") (class "Default")
      (node (ref "C25") (pin "+") (pinfunction "+_+") (pintype "passive"))
      (node (ref "IC5") (pin "3") (pinfunction "+IN_3") (pintype "input"))
      (node (ref "R36") (pin "1") (pinfunction "1_1") (pintype "passive"))
      (node (ref "R39") (pin "1") (pinfunction "1_1") (pintype "passive"))
      (node (ref "R40") (pin "2") (pinfunction "2_2") (pintype "passive"))
    )
    (net (code "52") (name "Net-(IC5A--IN)") (class "Default")
      (node (ref "C24") (pin "+") (pinfunction "+_+") (pintype "passive"))
      (node (ref "IC5") (pin "2") (pinfunction "-IN_2") (pintype "input"))
      (node (ref "R38") (pin "1") (pinfunction "1_1") (pintype "passive"))
    )
    (net (code "53") (name "Net-(IC5A-OUT)") (class "Default")
      (node (ref "C23") (pin "+") (pinfunction "+_+") (pintype "passive"))
      (node (ref "IC5") (pin "1") (pinfunction "OUT_1") (pintype "output"))
      (node (ref "R37") (pin "1") (pinfunction "1_1") (pintype "passive"))
      (node (ref "VR2") (pin "3") (pinfunction "E_3") (pintype "passive"))
    )
    (net (code "54") (name "Net-(IC5B-+IN)") (class "Default")
      (node (ref "IC5") (pin "5") (pinfunction "+IN_5") (pintype "input"))
      (node (ref "R35") (pin "1") (pinfunction "1_1") (pintype "passive"))
      (node (ref "R37") (pin "2") (pinfunction "2_2") (pintype "passive"))
    )
    (net (code "55") (name "Net-(IC5B--IN)") (class "Default")
      (node (ref "C22") (pin "1") (pinfunction "1_1") (pintype "passive"))
      (node (ref "IC5") (pin "6") (pinfunction "-IN_6") (pintype "input"))
      (node (ref "R36") (pin "2") (pinfunction "2_2") (pintype "passive"))
    )
    (net (code "56") (name "Net-(IC5B-OUT)") (class "Default")
      (node (ref "C22") (pin "2") (pinfunction "2_2") (pintype "passive"))
      (node (ref "IC5") (pin "7") (pinfunction "OUT_7") (pintype "output"))
      (node (ref "R35") (pin "2") (pinfunction "2_2") (pintype "passive"))
      (node (ref "VR3") (pin "3") (pinfunction "E_3") (pintype "passive"))
    )
    (net (code "57") (name "Net-(Q1-D)") (class "Default")
      (node (ref "C11") (pin "+") (pinfunction "+_+") (pintype "passive"))
      (node (ref "C33") (pin "+") (pinfunction "+_+") (pintype "passive"))
      (node (ref "Q1") (pin "1") (pinfunction "D_1") (pintype "passive"))
      (node (ref "R50") (pin "1") (pinfunction "1_1") (pintype "passive"))
    )
    (net (code "58") (name "Net-(Q1-G)") (class "Default")
      (node (ref "D4") (pin "A") (pinfunction "A_A") (pintype "passive"))
      (node (ref "Q1") (pin "2") (pinfunction "G_2") (pintype "passive"))
    )
    (net (code "59") (name "Net-(Q1-S)") (class "Default")
      (node (ref "C31") (pin "-") (pinfunction "-_-") (pintype "passive"))
      (node (ref "Q1") (pin "3") (pinfunction "S_3") (pintype "passive"))
      (node (ref "R49") (pin "1") (pinfunction "1_1") (pintype "passive"))
    )
    (net (code "60") (name "Net-(R3-Pad1)") (class "Default")
      (node (ref "R3") (pin "1") (pinfunction "1_1") (pintype "passive"))
      (node (ref "S1") (pin "3") (pinfunction "3_3") (pintype "passive"))
      (node (ref "S1") (pin "4") (pinfunction "4_4") (pintype "passive"))
    )
    (net (code "61") (name "Net-(R17-Pad2)") (class "Default")
      (node (ref "R17") (pin "2") (pinfunction "2_2") (pintype "passive"))
      (node (ref "SR3") (pin "E") (pinfunction "E_E") (pintype "passive"))
      (node (ref "SR3") (pin "S") (pinfunction "S_S") (pintype "passive"))
    )
    (net (code "62") (name "Net-(R25-Pad2)") (class "Default")
      (node (ref "R25") (pin "2") (pinfunction "2_2") (pintype "passive"))
      (node (ref "SR2") (pin "A") (pinfunction "A_A") (pintype "passive"))
    )
    (net (code "63") (name "Net-(R26-Pad2)") (class "Default")
      (node (ref "R26") (pin "2") (pinfunction "2_2") (pintype "passive"))
      (node (ref "SR2") (pin "E") (pinfunction "E_E") (pintype "passive"))
    )
    (net (code "64") (name "Net-(R27-Pad2)") (class "Default")
      (node (ref "R27") (pin "2") (pinfunction "2_2") (pintype "passive"))
      (node (ref "T5") (pin "C") (pinfunction "C_C") (pintype "passive"))
      (node (ref "T7") (pin "C") (pinfunction "C_C") (pintype "passive"))
    )
    (net (code "65") (name "Net-(R30-Pad2)") (class "Default")
      (node (ref "R30") (pin "2") (pinfunction "2_2") (pintype "passive"))
      (node (ref "R31") (pin "1") (pinfunction "1_1") (pintype "passive"))
      (node (ref "T6") (pin "B") (pinfunction "B_B") (pintype "passive"))
      (node (ref "T6") (pin "C") (pinfunction "C_C") (pintype "passive"))
    )
    (net (code "66") (name "Net-(R32-Pad2)") (class "Default")
      (node (ref "R32") (pin "2") (pinfunction "2_2") (pintype "passive"))
      (node (ref "SR1") (pin "S") (pinfunction "S_S") (pintype "passive"))
    )
    (net (code "67") (name "Net-(R33-Pad2)") (class "Default")
      (node (ref "R33") (pin "2") (pinfunction "2_2") (pintype "passive"))
      (node (ref "SR1") (pin "A") (pinfunction "A_A") (pintype "passive"))
    )
    (net (code "68") (name "Net-(VR1-E)") (class "Default")
      (node (ref "C11") (pin "-") (pinfunction "-_-") (pintype "passive"))
      (node (ref "VR1") (pin "3") (pinfunction "E_3") (pintype "passive"))
    )
    (net (code "69") (name "Net-(VR1-S)") (class "Default")
      (node (ref "C12") (pin "1") (pinfunction "1_1") (pintype "passive"))
      (node (ref "VR1") (pin "2") (pinfunction "S_2") (pintype "passive"))
    )
    (net (code "70") (name "Net-(VR2-A)") (class "Default")
      (node (ref "R62") (pin "2") (pinfunction "2_2") (pintype "passive"))
      (node (ref "T9") (pin "E") (pinfunction "E_E") (pintype "passive"))
      (node (ref "VR2") (pin "1") (pinfunction "A_1") (pintype "passive"))
    )
    (net (code "71") (name "Net-(VR2-S)") (class "Default")
      (node (ref "R34") (pin "1") (pinfunction "1_1") (pintype "passive"))
      (node (ref "VR2") (pin "2") (pinfunction "S_2") (pintype "passive"))
    )
    (net (code "72") (name "Net-(VR3-A)") (class "Default")
      (node (ref "R38") (pin "2") (pinfunction "2_2") (pintype "passive"))
      (node (ref "VR3") (pin "1") (pinfunction "A_1") (pintype "passive"))
      (node (ref "VR3") (pin "2") (pinfunction "S_2") (pintype "passive"))
    )
    (net (code "73") (name "Net-(VR4-S)") (class "Default")
      (node (ref "R61") (pin "2") (pinfunction "2_2") (pintype "passive"))
      (node (ref "VR4") (pin "2") (pinfunction "S_2") (pintype "passive"))
    )
    (net (code "74") (name "VCC") (class "Default")
      (node (ref "C1") (pin "+") (pinfunction "+_+") (pintype "passive"))
      (node (ref "C6") (pin "+") (pinfunction "+_+") (pintype "passive"))
      (node (ref "D1") (pin "C") (pinfunction "C_C") (pintype "passive"))
      (node (ref "IC1") (pin "8") (pinfunction "V+_8") (pintype "power_in"))
      (node (ref "IC2") (pin "8") (pinfunction "V+_8") (pintype "power_in"))
      (node (ref "IC6") (pin "3") (pinfunction "VI_3") (pintype "input"))
      (node (ref "J1") (pin "3") (pinfunction "3_3") (pintype "passive"))
      (node (ref "R1") (pin "1") (pinfunction "1_1") (pintype "passive"))
      (node (ref "R4") (pin "1") (pinfunction "1_1") (pintype "passive"))
      (node (ref "R8") (pin "2") (pinfunction "2_2") (pintype "passive"))
      (node (ref "R9") (pin "2") (pinfunction "2_2") (pintype "passive"))
      (node (ref "T4") (pin "C") (pinfunction "C_C") (pintype "passive"))
      (node (ref "T8") (pin "C") (pinfunction "C_C") (pintype "passive"))
    )
    (net (code "75") (name "unconnected-(C8-Pad1)") (class "Default")
      (node (ref "C8") (pin "1") (pinfunction "1_1") (pintype "passive"))
    )
    (net (code "76") (name "unconnected-(D5-PadC)") (class "Default")
      (node (ref "D5") (pin "C") (pinfunction "C_C") (pintype "passive"))
    )
    (net (code "77") (name "unconnected-(IC4-Pad6)") (class "Default")
      (node (ref "IC4") (pin "6") (pinfunction "6_6") (pintype "passive"))
    )
    (net (code "78") (name "unconnected-(J1-Pad2)") (class "Default")
      (node (ref "J1") (pin "2") (pinfunction "2_2") (pintype "passive"))
    )
    (net (code "79") (name "unconnected-(R11-Pad1)") (class "Default")
      (node (ref "R11") (pin "1") (pinfunction "1_1") (pintype "passive"))
    )
    (net (code "80") (name "unconnected-(R11-Pad2)") (class "Default")
      (node (ref "R11") (pin "2") (pinfunction "2_2") (pintype "passive"))
    )
    (net (code "81") (name "unconnected-(R58-Pad1)") (class "Default")
      (node (ref "R58") (pin "1") (pinfunction "1_1") (pintype "passive"))
    )
    (net (code "82") (name "unconnected-(T3-PadB)") (class "Default")
      (node (ref "T3") (pin "B") (pinfunction "B_B") (pintype "passive"))
    )
    (net (code "83") (name "unconnected-(T3-PadC)") (class "Default")
      (node (ref "T3") (pin "C") (pinfunction "C_C") (pintype "passive"))
    )
    (net (code "84") (name "unconnected-(T3-PadE)") (class "Default")
      (node (ref "T3") (pin "E") (pinfunction "E_E") (pintype "passive"))
    )
  )
)
